# moth_v2.net
KiCad netlist of a schematic drawn in EAGLE
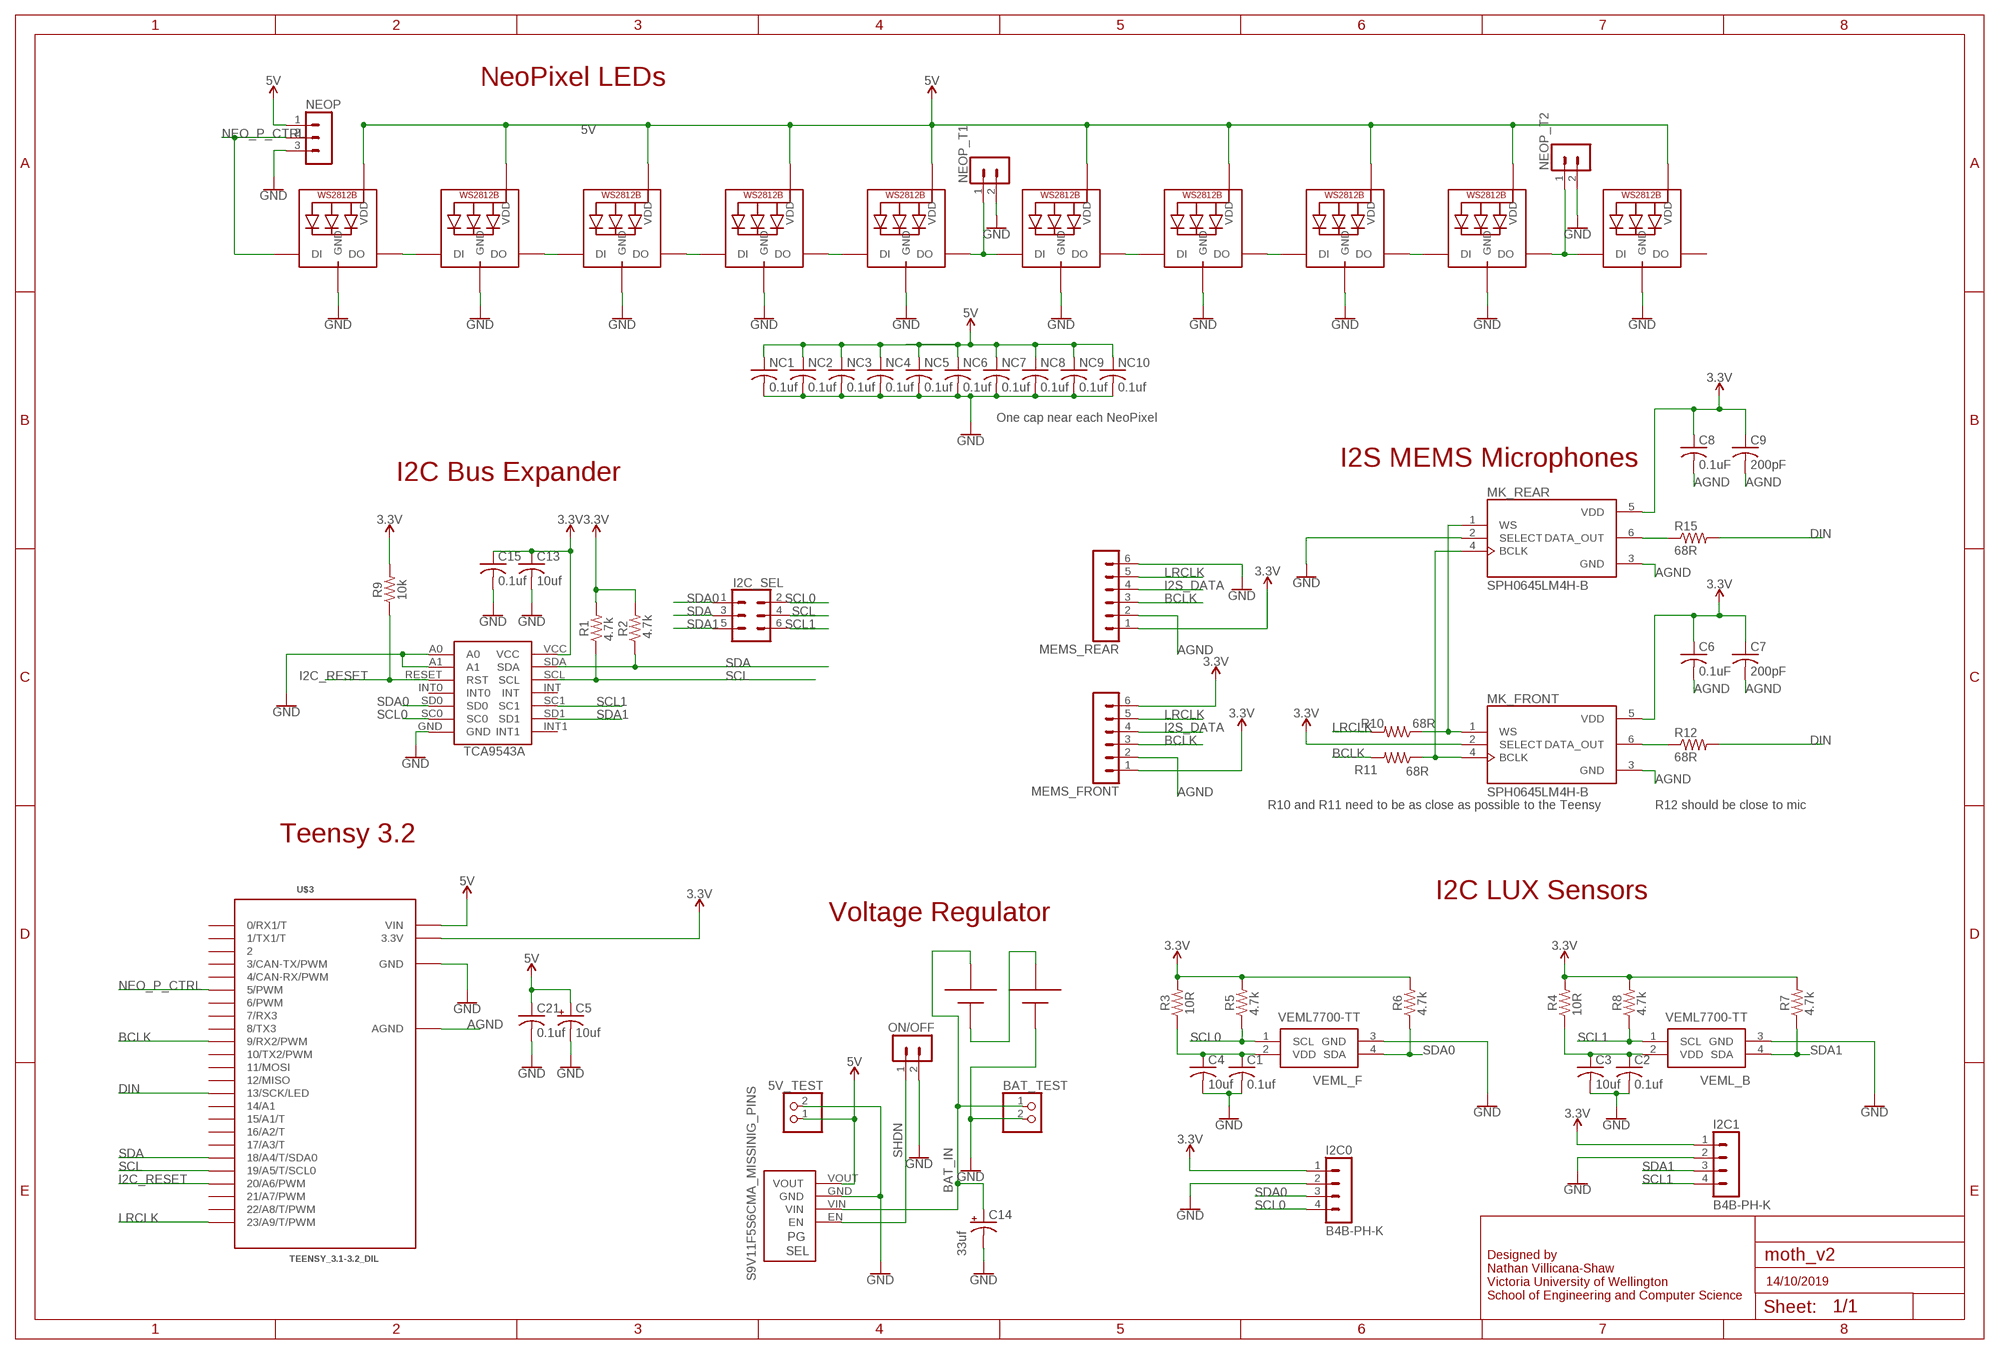
[diagram p0: schematic, sheet 1]

(export (version "E")
  (design (tool "Eeschema 10.0.6"))
  (components
    (comp (ref "5V_TEST")
      (value "PINHD-1X2")
      (footprint "eagle-import:1X02")
      (libsource (lib "eagle-import") (part "PINHD-1X2"))
    )
    (comp (ref "BAT_TEST")
      (value "PINHD-1X2")
      (footprint "eagle-import:1X02")
      (libsource (lib "eagle-import") (part "PINHD-1X2"))
    )
    (comp (ref "C1")
      (value "0.1uf")
      (footprint "eagle-import:C1206K")
      (libsource (lib "eagle-import") (part "C-USC1206K"))
    )
    (comp (ref "C2")
      (value "0.1uf")
      (footprint "eagle-import:C1206K")
      (libsource (lib "eagle-import") (part "C-USC1206K"))
    )
    (comp (ref "C3")
      (value "10uf")
      (footprint "eagle-import:C1206K")
      (libsource (lib "eagle-import") (part "C-USC1206K"))
    )
    (comp (ref "C4")
      (value "10uf")
      (footprint "eagle-import:C1206K")
      (libsource (lib "eagle-import") (part "C-USC1206K"))
    )
    (comp (ref "C5")
      (value "10uf")
      (footprint "eagle-import:E2,5-6")
      (libsource (lib "eagle-import") (part "CPOL-USE2.5-6"))
    )
    (comp (ref "C6")
      (value "0.1uF")
      (footprint "eagle-import:C1206K")
      (libsource (lib "eagle-import") (part "C-USC1206K"))
    )
    (comp (ref "C7")
      (value "200pF")
      (footprint "eagle-import:C1206K")
      (libsource (lib "eagle-import") (part "C-USC1206K"))
    )
    (comp (ref "C8")
      (value "0.1uF")
      (footprint "eagle-import:C1206K")
      (libsource (lib "eagle-import") (part "C-USC1206K"))
    )
    (comp (ref "C9")
      (value "200pF")
      (footprint "eagle-import:C1206K")
      (libsource (lib "eagle-import") (part "C-USC1206K"))
    )
    (comp (ref "C13")
      (value "10uf")
      (footprint "eagle-import:C1206K")
      (libsource (lib "eagle-import") (part "C-USC1206K"))
    )
    (comp (ref "C14")
      (value "33uf")
      (footprint "eagle-import:E2-5")
      (libsource (lib "eagle-import") (part "CPOL-USE2-5"))
    )
    (comp (ref "C15")
      (value "0.1uf")
      (footprint "eagle-import:C1206K")
      (libsource (lib "eagle-import") (part "C-USC1206K"))
    )
    (comp (ref "C21")
      (value "0.1uf")
      (footprint "eagle-import:C1206K")
      (libsource (lib "eagle-import") (part "C-USC1206K"))
    )
    (comp (ref "I2C0")
      (value "B4B-PH-K")
      (footprint "eagle-import:B4B-PH-K")
      (libsource (lib "eagle-import") (part "B4B-PH-K"))
    )
    (comp (ref "I2C1")
      (value "B4B-PH-K")
      (footprint "eagle-import:B4B-PH-K")
      (libsource (lib "eagle-import") (part "B4B-PH-K"))
    )
    (comp (ref "I2C_SEL")
      (value "FEMALE 2x3")
      (footprint "eagle-import:2X3")
      (libsource (lib "eagle-import") (part "CONN_03X2FEMALE"))
    )
    (comp (ref "MEMS_FRONT")
      (value "B6B-PH-K")
      (footprint "eagle-import:B6B-PH-K")
      (libsource (lib "eagle-import") (part "B6B-PH-K"))
    )
    (comp (ref "MEMS_REAR")
      (value "B6B-PH-K")
      (footprint "eagle-import:B6B-PH-K")
      (libsource (lib "eagle-import") (part "B6B-PH-K"))
    )
    (comp (ref "MK_FRONT")
      (value "SPH0645LM4H-B")
      (footprint "eagle-import:MIC_SPH0645LM4H-B")
      (fields (field (name "DIGI-KEY_PART_NUMBER") "423-1405-1-ND") (field (name "MF") "Knowles"))
      (libsource (lib "eagle-import") (part "SPH0645LM4H-B"))
    )
    (comp (ref "MK_REAR")
      (value "SPH0645LM4H-B")
      (footprint "eagle-import:MIC_SPH0645LM4H-B")
      (fields (field (name "DIGI-KEY_PART_NUMBER") "423-1405-1-ND") (field (name "MF") "Knowles"))
      (libsource (lib "eagle-import") (part "SPH0645LM4H-B"))
    )
    (comp (ref "NC1")
      (value "0.1uf")
      (footprint "eagle-import:C1206K")
      (libsource (lib "eagle-import") (part "C-USC1206K"))
    )
    (comp (ref "NC2")
      (value "0.1uf")
      (footprint "eagle-import:C1206K")
      (libsource (lib "eagle-import") (part "C-USC1206K"))
    )
    (comp (ref "NC3")
      (value "0.1uf")
      (footprint "eagle-import:C1206K")
      (libsource (lib "eagle-import") (part "C-USC1206K"))
    )
    (comp (ref "NC4")
      (value "0.1uf")
      (footprint "eagle-import:C1206K")
      (libsource (lib "eagle-import") (part "C-USC1206K"))
    )
    (comp (ref "NC5")
      (value "0.1uf")
      (footprint "eagle-import:C1206K")
      (libsource (lib "eagle-import") (part "C-USC1206K"))
    )
    (comp (ref "NC6")
      (value "0.1uf")
      (footprint "eagle-import:C1206K")
      (libsource (lib "eagle-import") (part "C-USC1206K"))
    )
    (comp (ref "NC7")
      (value "0.1uf")
      (footprint "eagle-import:C1206K")
      (libsource (lib "eagle-import") (part "C-USC1206K"))
    )
    (comp (ref "NC8")
      (value "0.1uf")
      (footprint "eagle-import:C1206K")
      (libsource (lib "eagle-import") (part "C-USC1206K"))
    )
    (comp (ref "NC9")
      (value "0.1uf")
      (footprint "eagle-import:C1206K")
      (libsource (lib "eagle-import") (part "C-USC1206K"))
    )
    (comp (ref "NC10")
      (value "0.1uf")
      (footprint "eagle-import:C1206K")
      (libsource (lib "eagle-import") (part "C-USC1206K"))
    )
    (comp (ref "NEO1")
      (value "WS2812B5050")
      (footprint "eagle-import:WS2812B")
      (libsource (lib "eagle-import") (part "WS2812B5050"))
    )
    (comp (ref "NEO2")
      (value "WS2812B5050")
      (footprint "eagle-import:WS2812B")
      (libsource (lib "eagle-import") (part "WS2812B5050"))
    )
    (comp (ref "NEO3")
      (value "WS2812B5050")
      (footprint "eagle-import:WS2812B")
      (libsource (lib "eagle-import") (part "WS2812B5050"))
    )
    (comp (ref "NEO4")
      (value "WS2812B5050")
      (footprint "eagle-import:WS2812B")
      (libsource (lib "eagle-import") (part "WS2812B5050"))
    )
    (comp (ref "NEO5")
      (value "WS2812B5050")
      (footprint "eagle-import:WS2812B")
      (libsource (lib "eagle-import") (part "WS2812B5050"))
    )
    (comp (ref "NEO6")
      (value "WS2812B5050")
      (footprint "eagle-import:WS2812B")
      (libsource (lib "eagle-import") (part "WS2812B5050"))
    )
    (comp (ref "NEO7")
      (value "WS2812B5050")
      (footprint "eagle-import:WS2812B")
      (libsource (lib "eagle-import") (part "WS2812B5050"))
    )
    (comp (ref "NEO8")
      (value "WS2812B5050")
      (footprint "eagle-import:WS2812B")
      (libsource (lib "eagle-import") (part "WS2812B5050"))
    )
    (comp (ref "NEO9")
      (value "WS2812B5050")
      (footprint "eagle-import:WS2812B")
      (libsource (lib "eagle-import") (part "WS2812B5050"))
    )
    (comp (ref "NEO10")
      (value "WS2812B5050")
      (footprint "eagle-import:WS2812B")
      (libsource (lib "eagle-import") (part "WS2812B5050"))
    )
    (comp (ref "NEOP")
      (value "B3B-PH-K")
      (footprint "eagle-import:B3B-PH-K")
      (libsource (lib "eagle-import") (part "B3B-PH-K"))
    )
    (comp (ref "NEOP_T1")
      (value "B2B-PH-K")
      (footprint "eagle-import:B2B-PH-K")
      (libsource (lib "eagle-import") (part "B2B-PH-K"))
    )
    (comp (ref "NEOP_T2")
      (value "B2B-PH-K")
      (footprint "eagle-import:B2B-PH-K")
      (libsource (lib "eagle-import") (part "B2B-PH-K"))
    )
    (comp (ref "ON/OFF")
      (value "B2B-PH-K")
      (footprint "eagle-import:B2B-PH-K")
      (libsource (lib "eagle-import") (part "B2B-PH-K"))
    )
    (comp (ref "R1")
      (value "4.7k")
      (footprint "eagle-import:R1206W")
      (libsource (lib "eagle-import") (part "R-US_R1206W"))
    )
    (comp (ref "R2")
      (value "4.7k")
      (footprint "eagle-import:R1206W")
      (libsource (lib "eagle-import") (part "R-US_R1206W"))
    )
    (comp (ref "R3")
      (value "10R")
      (footprint "eagle-import:R1206W")
      (libsource (lib "eagle-import") (part "R-US_R1206W"))
    )
    (comp (ref "R4")
      (value "10R")
      (footprint "eagle-import:R1206W")
      (libsource (lib "eagle-import") (part "R-US_R1206W"))
    )
    (comp (ref "R5")
      (value "4.7k")
      (footprint "eagle-import:R1206W")
      (libsource (lib "eagle-import") (part "R-US_R1206W"))
    )
    (comp (ref "R6")
      (value "4.7k")
      (footprint "eagle-import:R1206W")
      (libsource (lib "eagle-import") (part "R-US_R1206W"))
    )
    (comp (ref "R7")
      (value "4.7k")
      (footprint "eagle-import:R1206W")
      (libsource (lib "eagle-import") (part "R-US_R1206W"))
    )
    (comp (ref "R8")
      (value "4.7k")
      (footprint "eagle-import:R1206W")
      (libsource (lib "eagle-import") (part "R-US_R1206W"))
    )
    (comp (ref "R9")
      (value "10k")
      (footprint "eagle-import:R1206W")
      (libsource (lib "eagle-import") (part "R-US_R1206W"))
    )
    (comp (ref "R10")
      (value "68R")
      (footprint "eagle-import:M1206")
      (libsource (lib "eagle-import") (part "R-US_M1206"))
    )
    (comp (ref "R11")
      (value "68R")
      (footprint "eagle-import:M1206")
      (libsource (lib "eagle-import") (part "R-US_M1206"))
    )
    (comp (ref "R12")
      (value "68R")
      (footprint "eagle-import:M1206")
      (libsource (lib "eagle-import") (part "R-US_M1206"))
    )
    (comp (ref "R15")
      (value "68R")
      (footprint "eagle-import:M1206")
      (libsource (lib "eagle-import") (part "R-US_M1206"))
    )
    (comp (ref "U$1")
      (value "TCA9543A")
      (footprint "eagle-import:SO14")
      (libsource (lib "eagle-import") (part "TCA9543A"))
    )
    (comp (ref "U$2")
      (value "BK-18650-PC4")
      (footprint "eagle-import:18650-PC4")
      (fields (field (name "MF") "MPD"))
      (libsource (lib "eagle-import") (part "BK-18650-PC4"))
    )
    (comp (ref "U$3")
      (value "TEENSY_3.1-3.2_DIL")
      (footprint "eagle-import:TEENSY_3.0-3.2&LC_DIL")
      (libsource (lib "eagle-import") (part "TEENSY_3.1-3.2_DIL"))
    )
    (comp (ref "U$6")
      (value "S9V11F5S6CMA_MISSINIG_PINS")
      (footprint "eagle-import:S9V11F3S5CMA_MISSING_PINS")
      (libsource (lib "eagle-import") (part "S9V11F5S6CMA_MISSINIG_PINS"))
    )
    (comp (ref "VEML_B")
      (value "VEML7700-TT")
      (footprint "eagle-import:VEML7700")
      (fields (field (name "MOUSER_PART_NUMBER") "78-VEML7700-TT") (field (name "RS_PART_NUMBER") "1226791P"))
      (libsource (lib "eagle-import") (part "VEML7700-TT"))
    )
    (comp (ref "VEML_F")
      (value "VEML7700-TT")
      (footprint "eagle-import:VEML7700")
      (fields (field (name "MOUSER_PART_NUMBER") "78-VEML7700-TT") (field (name "RS_PART_NUMBER") "1226791P"))
      (libsource (lib "eagle-import") (part "VEML7700-TT"))
    )
  )
  (nets
    (net (code "1") (name "/AGND") (class "Default")
      (node (ref "C6") (pin "2") (pinfunction "2_2") (pintype "passive"))
      (node (ref "C7") (pin "2") (pinfunction "2_2") (pintype "passive"))
      (node (ref "C8") (pin "2") (pinfunction "2_2") (pintype "passive"))
      (node (ref "C9") (pin "2") (pinfunction "2_2") (pintype "passive"))
      (node (ref "MEMS_FRONT") (pin "2") (pinfunction "2_2") (pintype "passive"))
      (node (ref "MEMS_REAR") (pin "2") (pinfunction "2_2") (pintype "passive"))
      (node (ref "MK_FRONT") (pin "3") (pinfunction "GND_3") (pintype "power_in"))
      (node (ref "MK_REAR") (pin "3") (pinfunction "GND_3") (pintype "power_in"))
      (node (ref "U$3") (pin "AGND") (pinfunction "AGND_AGND") (pintype "power_in"))
    )
    (net (code "2") (name "/BAT_IN") (class "Default")
      (node (ref "BAT_TEST") (pin "1") (pinfunction "1_1") (pintype "passive"))
      (node (ref "C14") (pin "+") (pinfunction "+_+") (pintype "passive"))
      (node (ref "U$2") (pin "+1") (pinfunction "+1_+1") (pintype "bidirectional"))
      (node (ref "U$6") (pin "VIN") (pinfunction "VIN_VIN") (pintype "bidirectional"))
    )
    (net (code "3") (name "/BCLK") (class "Default")
      (node (ref "MEMS_FRONT") (pin "3") (pinfunction "3_3") (pintype "passive"))
      (node (ref "MEMS_REAR") (pin "3") (pinfunction "3_3") (pintype "passive"))
      (node (ref "R11") (pin "2") (pinfunction "2_2") (pintype "passive"))
      (node (ref "U$3") (pin "9") (pinfunction "9/RX2/PWM_9") (pintype "bidirectional"))
    )
    (net (code "4") (name "/DIN") (class "Default")
      (node (ref "R12") (pin "2") (pinfunction "2_2") (pintype "passive"))
      (node (ref "R15") (pin "2") (pinfunction "2_2") (pintype "passive"))
      (node (ref "U$3") (pin "13") (pinfunction "13/SCK/LED_13") (pintype "bidirectional"))
    )
    (net (code "5") (name "/I2C_RESET") (class "Default")
      (node (ref "R9") (pin "1") (pinfunction "1_1") (pintype "passive"))
      (node (ref "U$1") (pin "RESET") (pinfunction "RST_RESET") (pintype "bidirectional"))
      (node (ref "U$3") (pin "20/A6") (pinfunction "20/A6/PWM_20/A6") (pintype "bidirectional"))
    )
    (net (code "6") (name "/I2S_DATA") (class "Default")
      (node (ref "MEMS_FRONT") (pin "4") (pinfunction "4_4") (pintype "passive"))
      (node (ref "MEMS_REAR") (pin "4") (pinfunction "4_4") (pintype "passive"))
    )
    (net (code "7") (name "/LRCLK") (class "Default")
      (node (ref "MEMS_FRONT") (pin "5") (pinfunction "5_5") (pintype "passive"))
      (node (ref "MEMS_REAR") (pin "5") (pinfunction "5_5") (pintype "passive"))
      (node (ref "R10") (pin "2") (pinfunction "2_2") (pintype "passive"))
      (node (ref "U$3") (pin "23/A9") (pinfunction "23/A9/T/PWM_23/A9") (pintype "bidirectional"))
    )
    (net (code "8") (name "/NEO_P_CTRL") (class "Default")
      (node (ref "NEO1") (pin "4-DIN") (pinfunction "DI_4-DIN") (pintype "input"))
      (node (ref "NEOP") (pin "2") (pinfunction "2_2") (pintype "passive"))
      (node (ref "U$3") (pin "5") (pinfunction "5/PWM_5") (pintype "bidirectional"))
    )
    (net (code "9") (name "/SCL") (class "Default")
      (node (ref "I2C_SEL") (pin "4") (pinfunction "4_4") (pintype "bidirectional"))
      (node (ref "R1") (pin "1") (pinfunction "1_1") (pintype "passive"))
      (node (ref "U$1") (pin "SCL") (pinfunction "SCL_SCL") (pintype "bidirectional"))
      (node (ref "U$3") (pin "19/A5") (pinfunction "19/A5/T/SCL0_19/A5") (pintype "bidirectional"))
    )
    (net (code "10") (name "/SCL0") (class "Default")
      (node (ref "I2C0") (pin "4") (pinfunction "4_4") (pintype "passive"))
      (node (ref "I2C_SEL") (pin "2") (pinfunction "2_2") (pintype "bidirectional"))
      (node (ref "R5") (pin "1") (pinfunction "1_1") (pintype "passive"))
      (node (ref "U$1") (pin "SC0") (pinfunction "SC0_SC0") (pintype "bidirectional"))
      (node (ref "VEML_F") (pin "1") (pinfunction "SCL_1") (pintype "bidirectional"))
    )
    (net (code "11") (name "/SCL1") (class "Default")
      (node (ref "I2C1") (pin "4") (pinfunction "4_4") (pintype "passive"))
      (node (ref "I2C_SEL") (pin "6") (pinfunction "6_6") (pintype "bidirectional"))
      (node (ref "R8") (pin "1") (pinfunction "1_1") (pintype "passive"))
      (node (ref "U$1") (pin "SC1") (pinfunction "SC1_SC1") (pintype "bidirectional"))
      (node (ref "VEML_B") (pin "1") (pinfunction "SCL_1") (pintype "bidirectional"))
    )
    (net (code "12") (name "/SDA") (class "Default")
      (node (ref "I2C_SEL") (pin "3") (pinfunction "3_3") (pintype "bidirectional"))
      (node (ref "R2") (pin "1") (pinfunction "1_1") (pintype "passive"))
      (node (ref "U$1") (pin "SDA") (pinfunction "SDA_SDA") (pintype "bidirectional"))
      (node (ref "U$3") (pin "18/A4") (pinfunction "18/A4/T/SDA0_18/A4") (pintype "bidirectional"))
    )
    (net (code "13") (name "/SDA0") (class "Default")
      (node (ref "I2C0") (pin "3") (pinfunction "3_3") (pintype "passive"))
      (node (ref "I2C_SEL") (pin "1") (pinfunction "1_1") (pintype "bidirectional"))
      (node (ref "R6") (pin "1") (pinfunction "1_1") (pintype "passive"))
      (node (ref "U$1") (pin "SD0") (pinfunction "SD0_SD0") (pintype "bidirectional"))
      (node (ref "VEML_F") (pin "4") (pinfunction "SDA_4") (pintype "bidirectional"))
    )
    (net (code "14") (name "/SDA1") (class "Default")
      (node (ref "I2C1") (pin "3") (pinfunction "3_3") (pintype "passive"))
      (node (ref "I2C_SEL") (pin "5") (pinfunction "5_5") (pintype "bidirectional"))
      (node (ref "R7") (pin "1") (pinfunction "1_1") (pintype "passive"))
      (node (ref "U$1") (pin "SD1") (pinfunction "SD1_SD1") (pintype "bidirectional"))
      (node (ref "VEML_B") (pin "4") (pinfunction "SDA_4") (pintype "bidirectional"))
    )
    (net (code "15") (name "/SHDN") (class "Default")
      (node (ref "ON/OFF") (pin "1") (pinfunction "1_1") (pintype "passive"))
      (node (ref "U$6") (pin "EN") (pinfunction "EN_EN") (pintype "bidirectional"))
    )
    (net (code "16") (name "3.3V") (class "Default")
      (node (ref "C13") (pin "1") (pinfunction "1_1") (pintype "passive"))
      (node (ref "C15") (pin "1") (pinfunction "1_1") (pintype "passive"))
      (node (ref "C6") (pin "1") (pinfunction "1_1") (pintype "passive"))
      (node (ref "C7") (pin "1") (pinfunction "1_1") (pintype "passive"))
      (node (ref "C8") (pin "1") (pinfunction "1_1") (pintype "passive"))
      (node (ref "C9") (pin "1") (pinfunction "1_1") (pintype "passive"))
      (node (ref "I2C0") (pin "1") (pinfunction "1_1") (pintype "passive"))
      (node (ref "I2C1") (pin "1") (pinfunction "1_1") (pintype "passive"))
      (node (ref "MEMS_FRONT") (pin "1") (pinfunction "1_1") (pintype "passive"))
      (node (ref "MEMS_FRONT") (pin "6") (pinfunction "6_6") (pintype "passive"))
      (node (ref "MEMS_REAR") (pin "1") (pinfunction "1_1") (pintype "passive"))
      (node (ref "MK_FRONT") (pin "2") (pinfunction "SELECT_2") (pintype "input"))
      (node (ref "MK_FRONT") (pin "5") (pinfunction "VDD_5") (pintype "power_in"))
      (node (ref "MK_REAR") (pin "5") (pinfunction "VDD_5") (pintype "power_in"))
      (node (ref "R1") (pin "2") (pinfunction "2_2") (pintype "passive"))
      (node (ref "R2") (pin "2") (pinfunction "2_2") (pintype "passive"))
      (node (ref "R3") (pin "2") (pinfunction "2_2") (pintype "passive"))
      (node (ref "R4") (pin "2") (pinfunction "2_2") (pintype "passive"))
      (node (ref "R5") (pin "2") (pinfunction "2_2") (pintype "passive"))
      (node (ref "R6") (pin "2") (pinfunction "2_2") (pintype "passive"))
      (node (ref "R7") (pin "2") (pinfunction "2_2") (pintype "passive"))
      (node (ref "R8") (pin "2") (pinfunction "2_2") (pintype "passive"))
      (node (ref "R9") (pin "2") (pinfunction "2_2") (pintype "passive"))
      (node (ref "U$1") (pin "VCC") (pinfunction "VCC_VCC") (pintype "bidirectional"))
      (node (ref "U$3") (pin "3.3V") (pinfunction "3.3V_3.3V") (pintype "power_in"))
    )
    (net (code "17") (name "5V") (class "Default")
      (node (ref "5V_TEST") (pin "1") (pinfunction "1_1") (pintype "passive"))
      (node (ref "C21") (pin "1") (pinfunction "1_1") (pintype "passive"))
      (node (ref "C5") (pin "+") (pinfunction "+_+") (pintype "passive"))
      (node (ref "NC1") (pin "1") (pinfunction "1_1") (pintype "passive"))
      (node (ref "NC10") (pin "1") (pinfunction "1_1") (pintype "passive"))
      (node (ref "NC2") (pin "1") (pinfunction "1_1") (pintype "passive"))
      (node (ref "NC3") (pin "1") (pinfunction "1_1") (pintype "passive"))
      (node (ref "NC4") (pin "1") (pinfunction "1_1") (pintype "passive"))
      (node (ref "NC5") (pin "1") (pinfunction "1_1") (pintype "passive"))
      (node (ref "NC6") (pin "1") (pinfunction "1_1") (pintype "passive"))
      (node (ref "NC7") (pin "1") (pinfunction "1_1") (pintype "passive"))
      (node (ref "NC8") (pin "1") (pinfunction "1_1") (pintype "passive"))
      (node (ref "NC9") (pin "1") (pinfunction "1_1") (pintype "passive"))
      (node (ref "NEO1") (pin "1-VDD") (pinfunction "VDD_1-VDD") (pintype "power_in"))
      (node (ref "NEO10") (pin "1-VDD") (pinfunction "VDD_1-VDD") (pintype "power_in"))
      (node (ref "NEO2") (pin "1-VDD") (pinfunction "VDD_1-VDD") (pintype "power_in"))
      (node (ref "NEO3") (pin "1-VDD") (pinfunction "VDD_1-VDD") (pintype "power_in"))
      (node (ref "NEO4") (pin "1-VDD") (pinfunction "VDD_1-VDD") (pintype "power_in"))
      (node (ref "NEO5") (pin "1-VDD") (pinfunction "VDD_1-VDD") (pintype "power_in"))
      (node (ref "NEO6") (pin "1-VDD") (pinfunction "VDD_1-VDD") (pintype "power_in"))
      (node (ref "NEO7") (pin "1-VDD") (pinfunction "VDD_1-VDD") (pintype "power_in"))
      (node (ref "NEO8") (pin "1-VDD") (pinfunction "VDD_1-VDD") (pintype "power_in"))
      (node (ref "NEO9") (pin "1-VDD") (pinfunction "VDD_1-VDD") (pintype "power_in"))
      (node (ref "NEOP") (pin "1") (pinfunction "1_1") (pintype "passive"))
      (node (ref "U$3") (pin "VIN") (pinfunction "VIN_VIN") (pintype "power_in"))
      (node (ref "U$6") (pin "VOUT") (pinfunction "VOUT_VOUT") (pintype "bidirectional"))
    )
    (net (code "18") (name "GND") (class "Default")
      (node (ref "5V_TEST") (pin "2") (pinfunction "2_2") (pintype "passive"))
      (node (ref "BAT_TEST") (pin "2") (pinfunction "2_2") (pintype "passive"))
      (node (ref "C1") (pin "2") (pinfunction "2_2") (pintype "passive"))
      (node (ref "C13") (pin "2") (pinfunction "2_2") (pintype "passive"))
      (node (ref "C14") (pin "-") (pinfunction "-_-") (pintype "passive"))
      (node (ref "C15") (pin "2") (pinfunction "2_2") (pintype "passive"))
      (node (ref "C2") (pin "2") (pinfunction "2_2") (pintype "passive"))
      (node (ref "C21") (pin "2") (pinfunction "2_2") (pintype "passive"))
      (node (ref "C3") (pin "2") (pinfunction "2_2") (pintype "passive"))
      (node (ref "C4") (pin "2") (pinfunction "2_2") (pintype "passive"))
      (node (ref "C5") (pin "-") (pinfunction "-_-") (pintype "passive"))
      (node (ref "I2C0") (pin "2") (pinfunction "2_2") (pintype "passive"))
      (node (ref "I2C1") (pin "2") (pinfunction "2_2") (pintype "passive"))
      (node (ref "MEMS_REAR") (pin "6") (pinfunction "6_6") (pintype "passive"))
      (node (ref "MK_REAR") (pin "2") (pinfunction "SELECT_2") (pintype "input"))
      (node (ref "NC1") (pin "2") (pinfunction "2_2") (pintype "passive"))
      (node (ref "NC10") (pin "2") (pinfunction "2_2") (pintype "passive"))
      (node (ref "NC2") (pin "2") (pinfunction "2_2") (pintype "passive"))
      (node (ref "NC3") (pin "2") (pinfunction "2_2") (pintype "passive"))
      (node (ref "NC4") (pin "2") (pinfunction "2_2") (pintype "passive"))
      (node (ref "NC5") (pin "2") (pinfunction "2_2") (pintype "passive"))
      (node (ref "NC6") (pin "2") (pinfunction "2_2") (pintype "passive"))
      (node (ref "NC7") (pin "2") (pinfunction "2_2") (pintype "passive"))
      (node (ref "NC8") (pin "2") (pinfunction "2_2") (pintype "passive"))
      (node (ref "NC9") (pin "2") (pinfunction "2_2") (pintype "passive"))
      (node (ref "NEO1") (pin "3-GND") (pinfunction "GND_3-GND") (pintype "power_in"))
      (node (ref "NEO10") (pin "3-GND") (pinfunction "GND_3-GND") (pintype "power_in"))
      (node (ref "NEO2") (pin "3-GND") (pinfunction "GND_3-GND") (pintype "power_in"))
      (node (ref "NEO3") (pin "3-GND") (pinfunction "GND_3-GND") (pintype "power_in"))
      (node (ref "NEO4") (pin "3-GND") (pinfunction "GND_3-GND") (pintype "power_in"))
      (node (ref "NEO5") (pin "3-GND") (pinfunction "GND_3-GND") (pintype "power_in"))
      (node (ref "NEO6") (pin "3-GND") (pinfunction "GND_3-GND") (pintype "power_in"))
      (node (ref "NEO7") (pin "3-GND") (pinfunction "GND_3-GND") (pintype "power_in"))
      (node (ref "NEO8") (pin "3-GND") (pinfunction "GND_3-GND") (pintype "power_in"))
      (node (ref "NEO9") (pin "3-GND") (pinfunction "GND_3-GND") (pintype "power_in"))
      (node (ref "NEOP") (pin "3") (pinfunction "3_3") (pintype "passive"))
      (node (ref "NEOP_T1") (pin "2") (pinfunction "2_2") (pintype "passive"))
      (node (ref "NEOP_T2") (pin "2") (pinfunction "2_2") (pintype "passive"))
      (node (ref "ON/OFF") (pin "2") (pinfunction "2_2") (pintype "passive"))
      (node (ref "U$1") (pin "A0") (pinfunction "A0_A0") (pintype "bidirectional"))
      (node (ref "U$1") (pin "A1") (pinfunction "A1_A1") (pintype "bidirectional"))
      (node (ref "U$1") (pin "GND") (pinfunction "GND_GND") (pintype "bidirectional"))
      (node (ref "U$2") (pin "-2") (pinfunction "-2_-2") (pintype "bidirectional"))
      (node (ref "U$3") (pin "GND") (pinfunction "GND_GND") (pintype "power_in"))
      (node (ref "U$6") (pin "GND") (pinfunction "GND_GND") (pintype "bidirectional"))
      (node (ref "VEML_B") (pin "3") (pinfunction "GND_3") (pintype "bidirectional"))
      (node (ref "VEML_F") (pin "3") (pinfunction "GND_3") (pintype "bidirectional"))
    )
    (net (code "19") (name "Net-(MK_FRONT-BCLK)") (class "Default")
      (node (ref "MK_FRONT") (pin "4") (pinfunction "BCLK_4") (pintype "input"))
      (node (ref "MK_REAR") (pin "4") (pinfunction "BCLK_4") (pintype "input"))
      (node (ref "R11") (pin "1") (pinfunction "1_1") (pintype "passive"))
    )
    (net (code "20") (name "Net-(MK_FRONT-DATA_OUT)") (class "Default")
      (node (ref "MK_FRONT") (pin "6") (pinfunction "DATA_OUT_6") (pintype "output"))
      (node (ref "R12") (pin "1") (pinfunction "1_1") (pintype "passive"))
    )
    (net (code "21") (name "Net-(MK_FRONT-WS)") (class "Default")
      (node (ref "MK_FRONT") (pin "1") (pinfunction "WS_1") (pintype "input"))
      (node (ref "MK_REAR") (pin "1") (pinfunction "WS_1") (pintype "input"))
      (node (ref "R10") (pin "1") (pinfunction "1_1") (pintype "passive"))
    )
    (net (code "22") (name "Net-(MK_REAR-DATA_OUT)") (class "Default")
      (node (ref "MK_REAR") (pin "6") (pinfunction "DATA_OUT_6") (pintype "output"))
      (node (ref "R15") (pin "1") (pinfunction "1_1") (pintype "passive"))
    )
    (net (code "23") (name "Net-(NEO1-DO)") (class "Default")
      (node (ref "NEO1") (pin "2-DOUT") (pinfunction "DO_2-DOUT") (pintype "output"))
      (node (ref "NEO2") (pin "4-DIN") (pinfunction "DI_4-DIN") (pintype "input"))
    )
    (net (code "24") (name "Net-(NEO2-DO)") (class "Default")
      (node (ref "NEO2") (pin "2-DOUT") (pinfunction "DO_2-DOUT") (pintype "output"))
      (node (ref "NEO3") (pin "4-DIN") (pinfunction "DI_4-DIN") (pintype "input"))
    )
    (net (code "25") (name "Net-(NEO3-DO)") (class "Default")
      (node (ref "NEO3") (pin "2-DOUT") (pinfunction "DO_2-DOUT") (pintype "output"))
      (node (ref "NEO4") (pin "4-DIN") (pinfunction "DI_4-DIN") (pintype "input"))
    )
    (net (code "26") (name "Net-(NEO4-DO)") (class "Default")
      (node (ref "NEO4") (pin "2-DOUT") (pinfunction "DO_2-DOUT") (pintype "output"))
      (node (ref "NEO5") (pin "4-DIN") (pinfunction "DI_4-DIN") (pintype "input"))
    )
    (net (code "27") (name "Net-(NEO5-DO)") (class "Default")
      (node (ref "NEO5") (pin "2-DOUT") (pinfunction "DO_2-DOUT") (pintype "output"))
      (node (ref "NEO6") (pin "4-DIN") (pinfunction "DI_4-DIN") (pintype "input"))
      (node (ref "NEOP_T1") (pin "1") (pinfunction "1_1") (pintype "passive"))
    )
    (net (code "28") (name "Net-(NEO6-DO)") (class "Default")
      (node (ref "NEO6") (pin "2-DOUT") (pinfunction "DO_2-DOUT") (pintype "output"))
      (node (ref "NEO7") (pin "4-DIN") (pinfunction "DI_4-DIN") (pintype "input"))
    )
    (net (code "29") (name "Net-(NEO7-DO)") (class "Default")
      (node (ref "NEO7") (pin "2-DOUT") (pinfunction "DO_2-DOUT") (pintype "output"))
      (node (ref "NEO8") (pin "4-DIN") (pinfunction "DI_4-DIN") (pintype "input"))
    )
    (net (code "30") (name "Net-(NEO8-DO)") (class "Default")
      (node (ref "NEO8") (pin "2-DOUT") (pinfunction "DO_2-DOUT") (pintype "output"))
      (node (ref "NEO9") (pin "4-DIN") (pinfunction "DI_4-DIN") (pintype "input"))
    )
    (net (code "31") (name "Net-(NEO10-DI)") (class "Default")
      (node (ref "NEO10") (pin "4-DIN") (pinfunction "DI_4-DIN") (pintype "input"))
      (node (ref "NEO9") (pin "2-DOUT") (pinfunction "DO_2-DOUT") (pintype "output"))
      (node (ref "NEOP_T2") (pin "1") (pinfunction "1_1") (pintype "passive"))
    )
    (net (code "32") (name "Net-(U$2-Pad+2)") (class "Default")
      (node (ref "U$2") (pin "+2") (pinfunction "+2_+2") (pintype "bidirectional"))
      (node (ref "U$2") (pin "-1") (pinfunction "-1_-1") (pintype "bidirectional"))
    )
    (net (code "33") (name "Net-(VEML_B-VDD)") (class "Default")
      (node (ref "C2") (pin "1") (pinfunction "1_1") (pintype "passive"))
      (node (ref "C3") (pin "1") (pinfunction "1_1") (pintype "passive"))
      (node (ref "R4") (pin "1") (pinfunction "1_1") (pintype "passive"))
      (node (ref "VEML_B") (pin "2") (pinfunction "VDD_2") (pintype "bidirectional"))
    )
    (net (code "34") (name "Net-(VEML_F-VDD)") (class "Default")
      (node (ref "C1") (pin "1") (pinfunction "1_1") (pintype "passive"))
      (node (ref "C4") (pin "1") (pinfunction "1_1") (pintype "passive"))
      (node (ref "R3") (pin "1") (pinfunction "1_1") (pintype "passive"))
      (node (ref "VEML_F") (pin "2") (pinfunction "VDD_2") (pintype "bidirectional"))
    )
    (net (code "35") (name "unconnected-(NEO10-DO-Pad2-DOUT)") (class "Default")
      (node (ref "NEO10") (pin "2-DOUT") (pinfunction "DO_2-DOUT") (pintype "output"))
    )
    (net (code "36") (name "unconnected-(U$1-PadINT)") (class "Default")
      (node (ref "U$1") (pin "INT") (pinfunction "INT_INT") (pintype "bidirectional"))
    )
    (net (code "37") (name "unconnected-(U$1-PadINT0)") (class "Default")
      (node (ref "U$1") (pin "INT0") (pinfunction "INT0_INT0") (pintype "bidirectional"))
    )
    (net (code "38") (name "unconnected-(U$1-PadINT1)") (class "Default")
      (node (ref "U$1") (pin "INT1") (pinfunction "INT1_INT1") (pintype "bidirectional"))
    )
    (net (code "39") (name "unconnected-(U$3-0{slash}RX1{slash}T-Pad0)") (class "Default")
      (node (ref "U$3") (pin "0") (pinfunction "0/RX1/T_0") (pintype "bidirectional"))
    )
    (net (code "40") (name "unconnected-(U$3-1{slash}TX1{slash}T-Pad1)") (class "Default")
      (node (ref "U$3") (pin "1") (pinfunction "1/TX1/T_1") (pintype "bidirectional"))
    )
    (net (code "41") (name "unconnected-(U$3-3{slash}CAN-TX{slash}PWM-Pad3)") (class "Default")
      (node (ref "U$3") (pin "3") (pinfunction "3/CAN-TX/PWM_3") (pintype "bidirectional"))
    )
    (net (code "42") (name "unconnected-(U$3-4{slash}CAN-RX{slash}PWM-Pad4)") (class "Default")
      (node (ref "U$3") (pin "4") (pinfunction "4/CAN-RX/PWM_4") (pintype "bidirectional"))
    )
    (net (code "43") (name "unconnected-(U$3-6{slash}PWM-Pad6)") (class "Default")
      (node (ref "U$3") (pin "6") (pinfunction "6/PWM_6") (pintype "bidirectional"))
    )
    (net (code "44") (name "unconnected-(U$3-7{slash}RX3-Pad7)") (class "Default")
      (node (ref "U$3") (pin "7") (pinfunction "7/RX3_7") (pintype "bidirectional"))
    )
    (net (code "45") (name "unconnected-(U$3-8{slash}TX3-Pad8)") (class "Default")
      (node (ref "U$3") (pin "8") (pinfunction "8/TX3_8") (pintype "bidirectional"))
    )
    (net (code "46") (name "unconnected-(U$3-10{slash}TX2{slash}PWM-Pad10)") (class "Default")
      (node (ref "U$3") (pin "10") (pinfunction "10/TX2/PWM_10") (pintype "bidirectional"))
    )
    (net (code "47") (name "unconnected-(U$3-11{slash}MOSI-Pad11)") (class "Default")
      (node (ref "U$3") (pin "11") (pinfunction "11/MOSI_11") (pintype "bidirectional"))
    )
    (net (code "48") (name "unconnected-(U$3-12{slash}MISO-Pad12)") (class "Default")
      (node (ref "U$3") (pin "12") (pinfunction "12/MISO_12") (pintype "bidirectional"))
    )
    (net (code "49") (name "unconnected-(U$3-14{slash}A1-Pad14{slash}A0)") (class "Default")
      (node (ref "U$3") (pin "14/A0") (pinfunction "14/A1_14/A0") (pintype "bidirectional"))
    )
    (net (code "50") (name "unconnected-(U$3-15{slash}A1{slash}T-Pad15{slash}A1)") (class "Default")
      (node (ref "U$3") (pin "15/A1") (pinfunction "15/A1/T_15/A1") (pintype "bidirectional"))
    )
    (net (code "51") (name "unconnected-(U$3-16{slash}A2{slash}T-Pad16{slash}A2)") (class "Default")
      (node (ref "U$3") (pin "16/A2") (pinfunction "16/A2/T_16/A2") (pintype "bidirectional"))
    )
    (net (code "52") (name "unconnected-(U$3-17{slash}A3{slash}T-Pad17{slash}A3)") (class "Default")
      (node (ref "U$3") (pin "17/A3") (pinfunction "17/A3/T_17/A3") (pintype "bidirectional"))
    )
    (net (code "53") (name "unconnected-(U$3-21{slash}A7{slash}PWM-Pad21{slash}A7)") (class "Default")
      (node (ref "U$3") (pin "21/A7") (pinfunction "21/A7/PWM_21/A7") (pintype "bidirectional"))
    )
    (net (code "54") (name "unconnected-(U$3-22{slash}A8{slash}T{slash}PWM-Pad22{slash}A8)") (class "Default")
      (node (ref "U$3") (pin "22/A8") (pinfunction "22/A8/T/PWM_22/A8") (pintype "bidirectional"))
    )
    (net (code "55") (name "unconnected-(U$3-Pad2)") (class "Default")
      (node (ref "U$3") (pin "2") (pinfunction "2_2") (pintype "bidirectional"))
    )
  )
)
